# ICSL_PS_POWER.net
KiCad netlist of a schematic drawn in Altium Designer
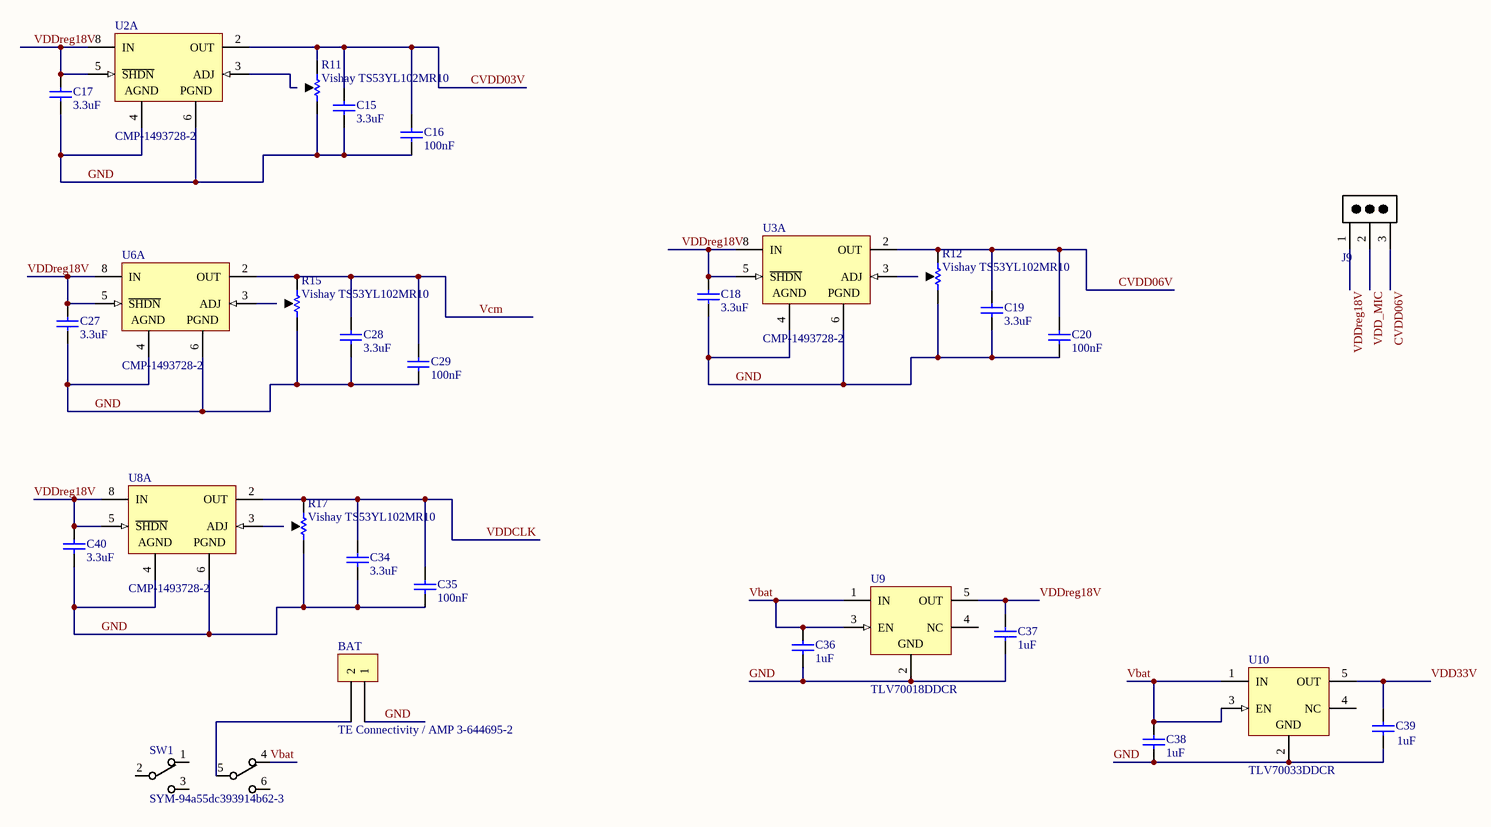
[diagram p0: ICSL_PS_POWER.SchDoc]

(export (version "E")
  (design (tool "Eeschema 10.0.6"))
  (components
    (comp (ref "BAT")
      (value "TE Connectivity / AMP 3-644695-2")
      (footprint "PCB-i8m17woc8q0u0fbeoczf-1")
      (description "Connector Unshrouded Header 2 Position 2.54mm Solder Straight Thru-Hole")
      (fields (field (name "MANUFACTURER PART NUMBER") "3-644695-2"))
      (libsource (lib "CommunityVault") (part "SYM-2792ecc2f21af855-1"))
    )
    (comp (ref "C15")
      (value "3.3uF")
      (description "CAP CER 1500PF 50V 10% X7R 0805")
      (fields (field (name "MANUFACTURER PART NUMBER") "08055C152KAT2A"))
      (libsource (lib "CommunityVault") (part "CMP-126016-2"))
    )
    (comp (ref "C16")
      (value "100nF")
      (footprint "CAPC1608X90X35NL15T15")
      (description "Multilayer Ceramic Capacitors MLCC - SMD/SMT 0603 10uF 4VOLTS X5R 10%")
      (fields (field (name "MANUFACTURER PART NUMBER") "06034D106KAT2A") (field (name "TOLERANCE") "10 %"))
      (libsource (lib "CommunityVault") (part "CMP-4105021-1"))
    )
    (comp (ref "C17")
      (value "3.3uF")
      (description "CAP CER 1500PF 50V 10% X7R 0805")
      (fields (field (name "MANUFACTURER PART NUMBER") "08055C152KAT2A"))
      (libsource (lib "CommunityVault") (part "CMP-126016-2"))
    )
    (comp (ref "C18")
      (value "3.3uF")
      (description "CAP CER 1500PF 50V 10% X7R 0805")
      (fields (field (name "MANUFACTURER PART NUMBER") "08055C152KAT2A"))
      (libsource (lib "CommunityVault") (part "CMP-126016-2"))
    )
    (comp (ref "C19")
      (value "3.3uF")
      (footprint "CAPC2013X94X50LL20T25")
      (description "CAP CER 1500PF 50V 10% X7R 0805")
      (libsource (lib "CommunityVault") (part "CMP-126016-2"))
    )
    (comp (ref "C20")
      (value "100nF")
      (footprint "CAPC1608X90X35NL15T15")
      (description "Multilayer Ceramic Capacitors MLCC - SMD/SMT 0603 10uF 4VOLTS X5R 10%")
      (fields (field (name "MANUFACTURER PART NUMBER") "06034D106KAT2A") (field (name "TOLERANCE") "10 %"))
      (libsource (lib "CommunityVault") (part "CMP-4105021-1"))
    )
    (comp (ref "C27")
      (value "3.3uF")
      (footprint "CAPC2013X94X50LL20T25")
      (description "CAP CER 1500PF 50V 10% X7R 0805")
      (libsource (lib "CommunityVault") (part "CMP-126016-2"))
    )
    (comp (ref "C28")
      (value "3.3uF")
      (footprint "CAPC2013X94X50LL20T25")
      (description "CAP CER 1500PF 50V 10% X7R 0805")
      (libsource (lib "CommunityVault") (part "CMP-126016-2"))
    )
    (comp (ref "C29")
      (value "100nF")
      (footprint "CAPC1608X90X35NL15T15")
      (description "Multilayer Ceramic Capacitors MLCC - SMD/SMT 0603 10uF 4VOLTS X5R 10%")
      (fields (field (name "MANUFACTURER PART NUMBER") "06034D106KAT2A") (field (name "TOLERANCE") "10 %"))
      (libsource (lib "CommunityVault") (part "CMP-4105021-1"))
    )
    (comp (ref "C34")
      (value "3.3uF")
      (footprint "CAPC2013X94X50LL20T25")
      (description "CAP CER 1500PF 50V 10% X7R 0805")
      (libsource (lib "CommunityVault") (part "CMP-126016-2"))
    )
    (comp (ref "C35")
      (value "100nF")
      (footprint "CAPC1608X90X35NL15T15")
      (description "Multilayer Ceramic Capacitors MLCC - SMD/SMT 0603 10uF 4VOLTS X5R 10%")
      (fields (field (name "MANUFACTURER PART NUMBER") "06034D106KAT2A") (field (name "TOLERANCE") "10 %"))
      (libsource (lib "CommunityVault") (part "CMP-4105021-1"))
    )
    (comp (ref "C36")
      (value "1uF")
      (footprint "CAPC2013X94X50LL20T25")
      (description "CAP CER 1500PF 50V 10% X7R 0805")
      (libsource (lib "CommunityVault") (part "CMP-126016-2"))
    )
    (comp (ref "C37")
      (value "1uF")
      (footprint "CAPC2013X94X50LL20T25")
      (description "CAP CER 1500PF 50V 10% X7R 0805")
      (libsource (lib "CommunityVault") (part "CMP-126016-2"))
    )
    (comp (ref "C38")
      (value "1uF")
      (footprint "CAPC2013X94X50LL20T25")
      (description "CAP CER 1500PF 50V 10% X7R 0805")
      (libsource (lib "CommunityVault") (part "CMP-126016-2"))
    )
    (comp (ref "C39")
      (value "1uF")
      (footprint "CAPC2013X94X50LL20T25")
      (description "CAP CER 1500PF 50V 10% X7R 0805")
      (libsource (lib "CommunityVault") (part "CMP-126016-2"))
    )
    (comp (ref "C40")
      (value "3.3uF")
      (footprint "CAPC2013X94X50LL20T25")
      (description "CAP CER 1500PF 50V 10% X7R 0805")
      (libsource (lib "CommunityVault") (part "CMP-126016-2"))
    )
    (comp (ref "J9")
      (value "3M 961103-6404-AR")
      (footprint "JP2")
      (description "CONN HEADER VERT SGL 3POS GOLD")
      (libsource (lib "Octopart library") (part "Header_3x1"))
    )
    (comp (ref "R11")
      (value "Vishay TS53YL102MR10")
      (footprint "PCB-2411124-1")
      (description "TRIMMER 1K OHM 0.25W SMD")
      (libsource (lib "Octopart library") (part "SYM-2411124-1"))
    )
    (comp (ref "R12")
      (value "Vishay TS53YL102MR10")
      (footprint "PCB-2411124-1")
      (description "TRIMMER 1K OHM 0.25W SMD")
      (libsource (lib "CommunityVault") (part "SYM-2411124-1"))
    )
    (comp (ref "R15")
      (value "Vishay TS53YL102MR10")
      (footprint "PCB-2411124-1")
      (description "TRIMMER 1K OHM 0.25W SMD")
      (libsource (lib "CommunityVault") (part "SYM-2411124-1"))
    )
    (comp (ref "R17")
      (value "Vishay TS53YL102MR10")
      (footprint "PCB-2411124-1")
      (description "TRIMMER 1K OHM 0.25W SMD")
      (libsource (lib "CommunityVault") (part "CMP-2411124-3"))
    )
    (comp (ref "SW1")
      (value "SYM-94a55dc393914b62-3")
      (footprint "PCB-ixy6r264hz8u4okoxsrw-1")
      (description "Slide Switch DPDT Surface Mount")
      (fields (field (name "MANUFACTURER") "C&K") (field (name "VENDOR PART NUMBER") "401-2002-1-ND"))
      (libsource (lib "Octopart library") (part "SYM-94a55dc393914b62-3"))
    )
    (comp (ref "U2")
      (value "CMP-1493728-2")
      (footprint "LT-S8-8_N")
      (libsource (lib "CommunityVault") (part "LT-LT3021-S8-8_B"))
    )
    (comp (ref "U3")
      (value "CMP-1493728-2")
      (footprint "LT-S8-8_N")
      (libsource (lib "CommunityVault") (part "CMP-1493728-2"))
    )
    (comp (ref "U6")
      (value "CMP-1493728-2")
      (footprint "LT-S8-8_N")
      (libsource (lib "CommunityVault") (part "CMP-1493728-2"))
    )
    (comp (ref "U8")
      (value "CMP-1493728-2")
      (footprint "LT-S8-8_N")
      (libsource (lib "CommunityVault") (part "CMP-1493728-2"))
    )
    (comp (ref "U9")
      (value "TLV70018DDCR")
      (footprint "TI-DDC5_L")
      (libsource (lib "Octopart library") (part "TI-TXX7XXXX-5"))
    )
    (comp (ref "U10")
      (value "TLV70033DDCR")
      (footprint "PCB-o8wu4fpdtd8bqe2xojjk-1")
      (libsource (lib "Octopart library") (part "TI-TXX7XXXX-5"))
    )
  )
  (nets
    (net (code "1") (name "/CVDD03V") (class "Default")
      (node (ref "C15") (pin "2") (pinfunction "2_2") (pintype "passive"))
      (node (ref "C16") (pin "1") (pinfunction "1_1") (pintype "passive"))
      (node (ref "R11") (pin "1") (pinfunction "1_1") (pintype "passive"))
      (node (ref "U2") (pin "2") (pinfunction "OUT_2") (pintype "power_in"))
    )
    (net (code "2") (name "/CVDD06V") (class "Default")
      (node (ref "C19") (pin "2") (pinfunction "2_2") (pintype "passive"))
      (node (ref "C20") (pin "1") (pinfunction "1_1") (pintype "passive"))
      (node (ref "J9") (pin "3") (pinfunction "3_3") (pintype "passive"))
      (node (ref "R12") (pin "1") (pinfunction "1_1") (pintype "passive"))
      (node (ref "U3") (pin "2") (pinfunction "OUT_2") (pintype "power_in"))
    )
    (net (code "3") (name "/GND") (class "Default")
      (node (ref "BAT") (pin "1") (pinfunction "1_1") (pintype "passive"))
      (node (ref "C15") (pin "1") (pinfunction "1_1") (pintype "passive"))
      (node (ref "C16") (pin "2") (pinfunction "2_2") (pintype "passive"))
      (node (ref "C17") (pin "1") (pinfunction "1_1") (pintype "passive"))
      (node (ref "C18") (pin "1") (pinfunction "1_1") (pintype "passive"))
      (node (ref "C19") (pin "1") (pinfunction "1_1") (pintype "passive"))
      (node (ref "C20") (pin "2") (pinfunction "2_2") (pintype "passive"))
      (node (ref "C27") (pin "1") (pinfunction "1_1") (pintype "passive"))
      (node (ref "C28") (pin "1") (pinfunction "1_1") (pintype "passive"))
      (node (ref "C29") (pin "1") (pinfunction "1_1") (pintype "passive"))
      (node (ref "C34") (pin "1") (pinfunction "1_1") (pintype "passive"))
      (node (ref "C35") (pin "1") (pinfunction "1_1") (pintype "passive"))
      (node (ref "C36") (pin "1") (pinfunction "1_1") (pintype "passive"))
      (node (ref "C37") (pin "1") (pinfunction "1_1") (pintype "passive"))
      (node (ref "C38") (pin "1") (pinfunction "1_1") (pintype "passive"))
      (node (ref "C39") (pin "2") (pinfunction "2_2") (pintype "passive"))
      (node (ref "C40") (pin "1") (pinfunction "1_1") (pintype "passive"))
      (node (ref "R11") (pin "3") (pinfunction "3_3") (pintype "passive"))
      (node (ref "R12") (pin "3") (pinfunction "3_3") (pintype "passive"))
      (node (ref "R15") (pin "3") (pinfunction "3_3") (pintype "passive"))
      (node (ref "R17") (pin "3") (pinfunction "3_3") (pintype "passive"))
      (node (ref "U10") (pin "2") (pinfunction "GND_2") (pintype "power_in"))
      (node (ref "U2") (pin "4") (pinfunction "AGND_4") (pintype "power_in"))
      (node (ref "U2") (pin "6") (pinfunction "PGND_6") (pintype "power_in"))
      (node (ref "U3") (pin "4") (pinfunction "AGND_4") (pintype "power_in"))
      (node (ref "U3") (pin "6") (pinfunction "PGND_6") (pintype "power_in"))
      (node (ref "U6") (pin "4") (pinfunction "AGND_4") (pintype "power_in"))
      (node (ref "U6") (pin "6") (pinfunction "PGND_6") (pintype "power_in"))
      (node (ref "U8") (pin "4") (pinfunction "AGND_4") (pintype "power_in"))
      (node (ref "U8") (pin "6") (pinfunction "PGND_6") (pintype "power_in"))
      (node (ref "U9") (pin "2") (pinfunction "GND_2") (pintype "power_in"))
    )
    (net (code "4") (name "/VDD33V") (class "Default")
      (node (ref "C39") (pin "1") (pinfunction "1_1") (pintype "passive"))
      (node (ref "U10") (pin "5") (pinfunction "OUT_5") (pintype "power_in"))
    )
    (net (code "5") (name "/VDDCLK") (class "Default")
      (node (ref "C34") (pin "2") (pinfunction "2_2") (pintype "passive"))
      (node (ref "C35") (pin "2") (pinfunction "2_2") (pintype "passive"))
      (node (ref "R17") (pin "1") (pinfunction "1_1") (pintype "passive"))
      (node (ref "U8") (pin "2") (pinfunction "OUT_2") (pintype "power_in"))
    )
    (net (code "6") (name "/VDD_MIC") (class "Default")
      (node (ref "J9") (pin "2") (pinfunction "2_2") (pintype "passive"))
    )
    (net (code "7") (name "/VDDreg18V") (class "Default")
      (node (ref "C17") (pin "2") (pinfunction "2_2") (pintype "passive"))
      (node (ref "C18") (pin "2") (pinfunction "2_2") (pintype "passive"))
      (node (ref "C27") (pin "2") (pinfunction "2_2") (pintype "passive"))
      (node (ref "C37") (pin "2") (pinfunction "2_2") (pintype "passive"))
      (node (ref "C40") (pin "2") (pinfunction "2_2") (pintype "passive"))
      (node (ref "J9") (pin "1") (pinfunction "1_1") (pintype "passive"))
      (node (ref "U2") (pin "5") (pinfunction "~{SHDN}_5") (pintype "input"))
      (node (ref "U2") (pin "8") (pinfunction "IN_8") (pintype "power_in"))
      (node (ref "U3") (pin "5") (pinfunction "~{SHDN}_5") (pintype "input"))
      (node (ref "U3") (pin "8") (pinfunction "IN_8") (pintype "power_in"))
      (node (ref "U6") (pin "5") (pinfunction "~{SHDN}_5") (pintype "input"))
      (node (ref "U6") (pin "8") (pinfunction "IN_8") (pintype "power_in"))
      (node (ref "U8") (pin "5") (pinfunction "~{SHDN}_5") (pintype "input"))
      (node (ref "U8") (pin "8") (pinfunction "IN_8") (pintype "power_in"))
      (node (ref "U9") (pin "5") (pinfunction "OUT_5") (pintype "power_in"))
    )
    (net (code "8") (name "/Vbat") (class "Default")
      (node (ref "C36") (pin "2") (pinfunction "2_2") (pintype "passive"))
      (node (ref "C38") (pin "2") (pinfunction "2_2") (pintype "passive"))
      (node (ref "SW1") (pin "4") (pinfunction "4_4") (pintype "passive"))
      (node (ref "U10") (pin "1") (pinfunction "IN_1") (pintype "power_in"))
      (node (ref "U10") (pin "3") (pinfunction "EN_3") (pintype "input"))
      (node (ref "U9") (pin "1") (pinfunction "IN_1") (pintype "power_in"))
      (node (ref "U9") (pin "3") (pinfunction "EN_3") (pintype "input"))
    )
    (net (code "9") (name "/Vcm") (class "Default")
      (node (ref "C28") (pin "2") (pinfunction "2_2") (pintype "passive"))
      (node (ref "C29") (pin "2") (pinfunction "2_2") (pintype "passive"))
      (node (ref "R15") (pin "1") (pinfunction "1_1") (pintype "passive"))
      (node (ref "U6") (pin "2") (pinfunction "OUT_2") (pintype "power_in"))
    )
    (net (code "10") (name "Net-(BAT-Pad2)") (class "Default")
      (node (ref "BAT") (pin "2") (pinfunction "2_2") (pintype "passive"))
      (node (ref "SW1") (pin "5") (pinfunction "5_5") (pintype "passive"))
    )
    (net (code "11") (name "Net-(U2A-ADJ)") (class "Default")
      (node (ref "R11") (pin "2") (pinfunction "2_2") (pintype "passive"))
      (node (ref "U2") (pin "3") (pinfunction "ADJ_3") (pintype "input"))
    )
    (net (code "12") (name "Net-(U3A-ADJ)") (class "Default")
      (node (ref "R12") (pin "2") (pinfunction "2_2") (pintype "passive"))
      (node (ref "U3") (pin "3") (pinfunction "ADJ_3") (pintype "input"))
    )
    (net (code "13") (name "Net-(U6A-ADJ)") (class "Default")
      (node (ref "R15") (pin "2") (pinfunction "2_2") (pintype "passive"))
      (node (ref "U6") (pin "3") (pinfunction "ADJ_3") (pintype "input"))
    )
    (net (code "14") (name "Net-(U8A-ADJ)") (class "Default")
      (node (ref "R17") (pin "2") (pinfunction "2_2") (pintype "passive"))
      (node (ref "U8") (pin "3") (pinfunction "ADJ_3") (pintype "input"))
    )
    (net (code "15") (name "unconnected-(SW1-Pad1)") (class "Default")
      (node (ref "SW1") (pin "1") (pinfunction "1_1") (pintype "passive"))
    )
    (net (code "16") (name "unconnected-(SW1-Pad2)") (class "Default")
      (node (ref "SW1") (pin "2") (pinfunction "2_2") (pintype "passive"))
    )
    (net (code "17") (name "unconnected-(SW1-Pad3)") (class "Default")
      (node (ref "SW1") (pin "3") (pinfunction "3_3") (pintype "passive"))
    )
    (net (code "18") (name "unconnected-(SW1-Pad6)") (class "Default")
      (node (ref "SW1") (pin "6") (pinfunction "6_6") (pintype "passive"))
    )
    (net (code "19") (name "unconnected-(U9-NC-Pad4)") (class "Default")
      (node (ref "U9") (pin "4") (pinfunction "NC_4") (pintype "passive"))
    )
    (net (code "20") (name "unconnected-(U10-NC-Pad4)") (class "Default")
      (node (ref "U10") (pin "4") (pinfunction "NC_4") (pintype "passive"))
    )
  )
)
